# shudian_datapath.net
KiCad netlist of a schematic drawn in Altium Designer
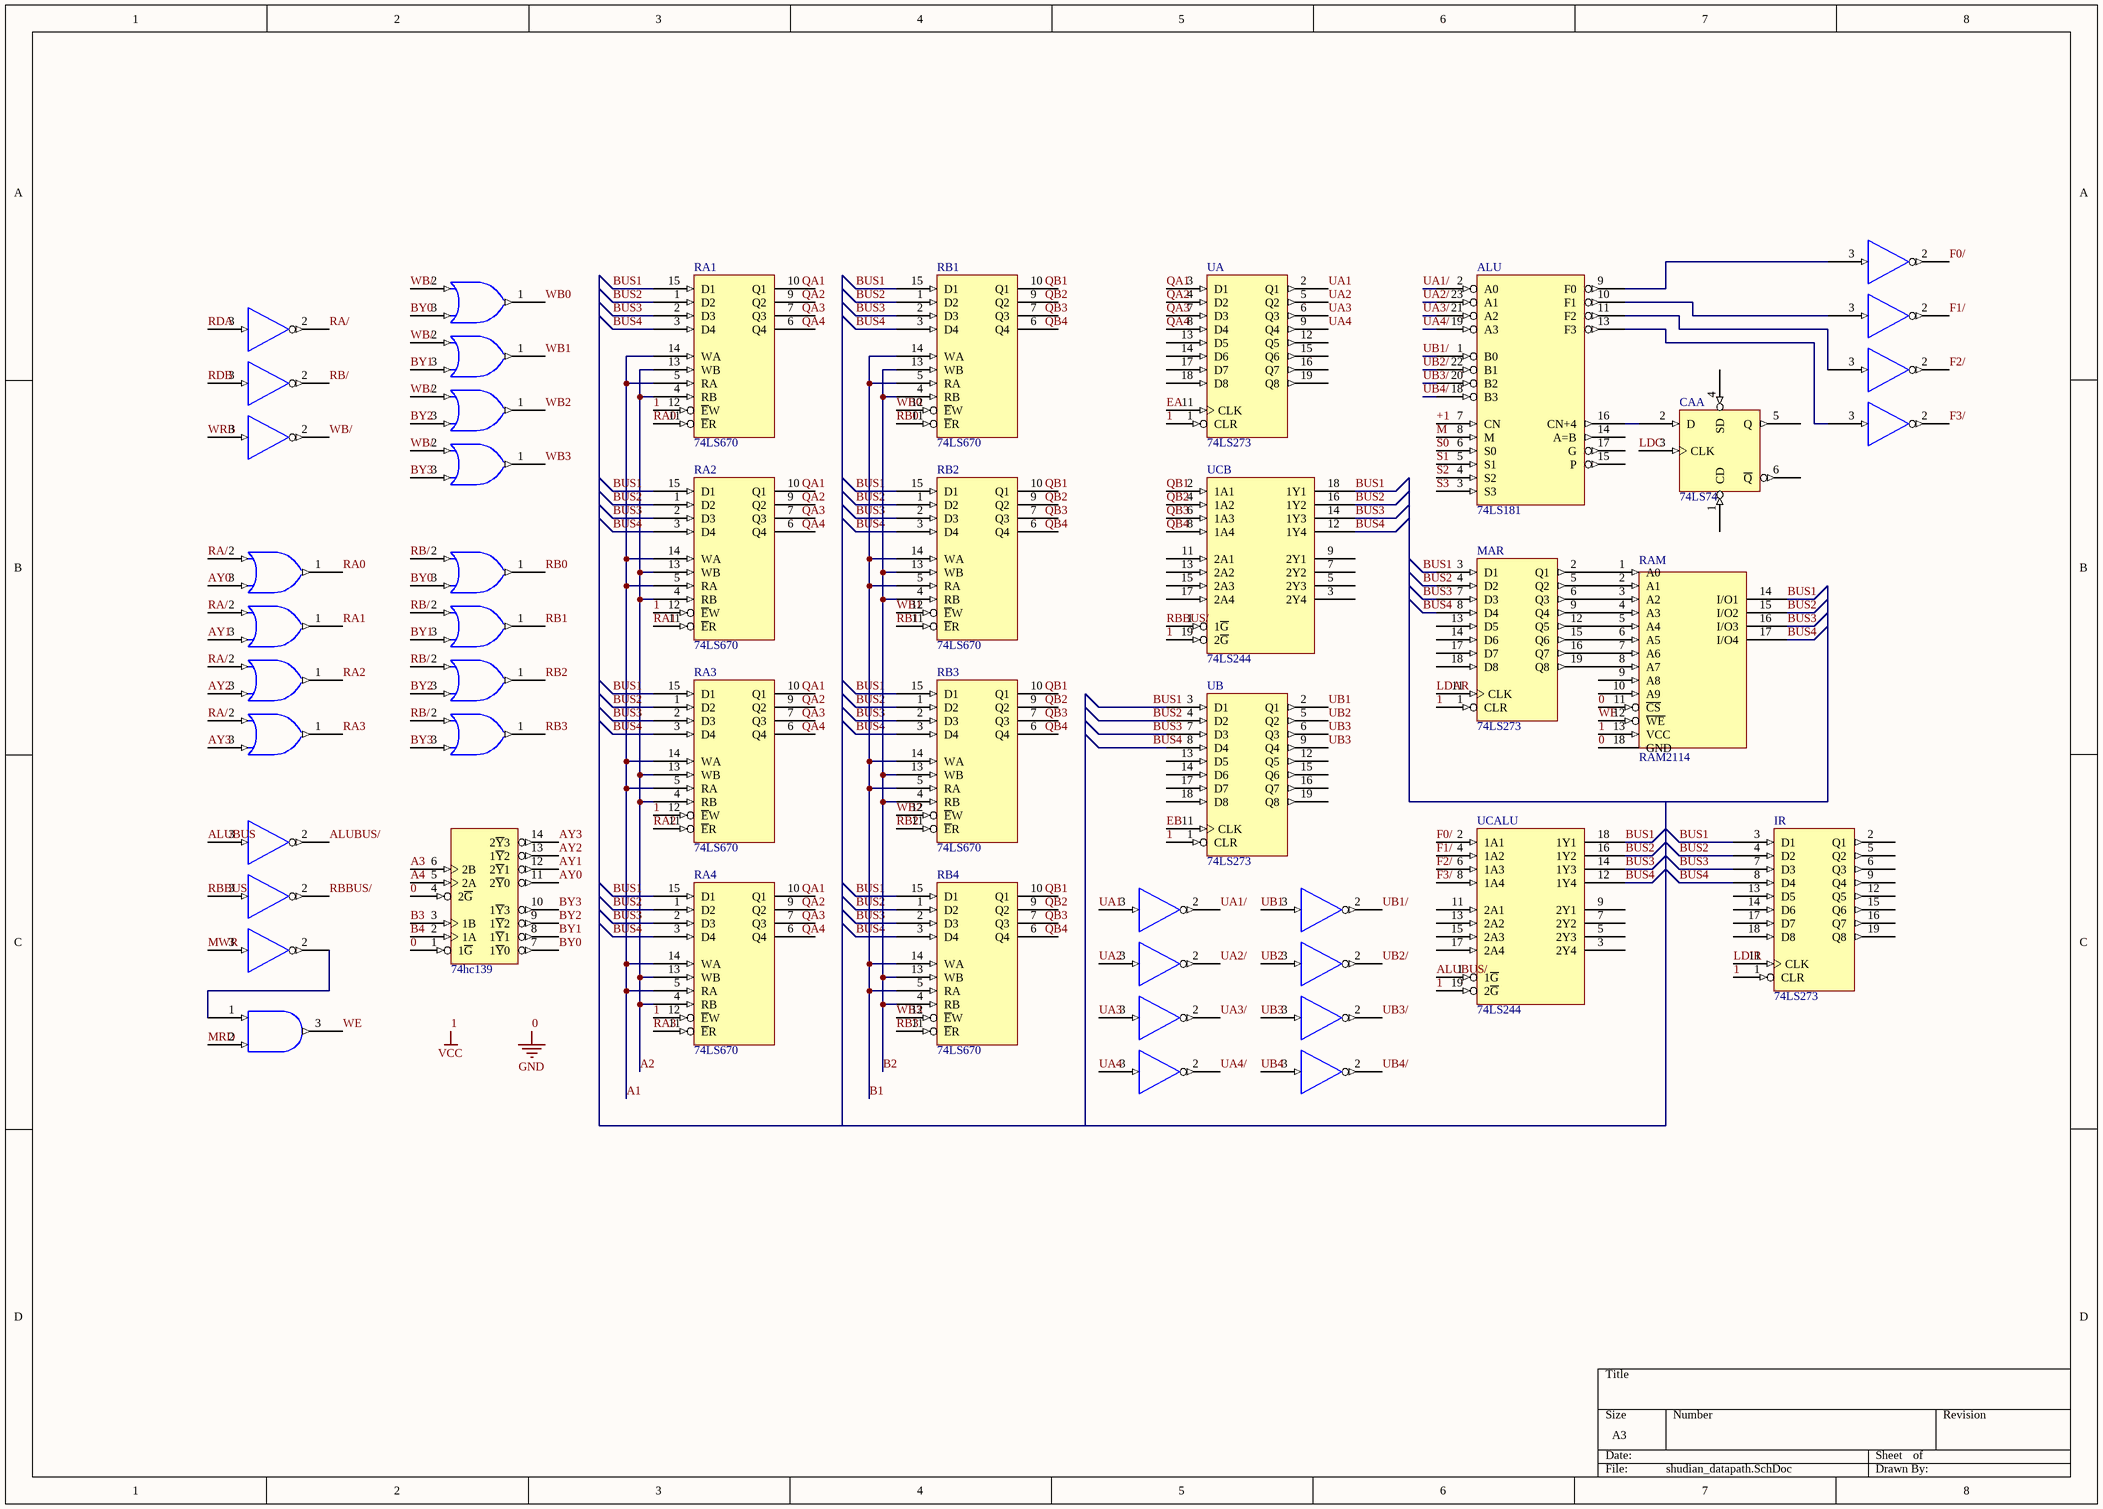
[diagram p0: shudian_datapath.SchDoc]

(export (version "E")
  (design (tool "Eeschema 10.0.6"))
  (components
    (comp (ref "*1") (value "not") (libsource (lib "数电") (part "not")))
    (comp (ref "*2") (value "not") (libsource (lib "数电") (part "not")))
    (comp (ref "*3") (value "not") (libsource (lib "数电") (part "not")))
    (comp (ref "*4-2") (value "74hc139") (libsource (lib "数电") (part "74hc139")))
    (comp (ref "*21") (value "and") (libsource (lib "数电") (part "and")))
    (comp (ref "*or5") (value "or") (libsource (lib "数电") (part "or")))
    (comp (ref "ALU") (value "74LS181") (footprint "DIP-24") (libsource (lib "数电") (part "74LS181")))
    (comp (ref "CA") (value "74LS74") (footprint "DIP-14") (libsource (lib "数电") (part "74LS74")))
    (comp (ref "IR") (value "74LS273") (footprint "DIP-20") (libsource (lib "数电") (part "74LS273")))
    (comp (ref "MAR") (value "74LS273") (footprint "DIP-20") (libsource (lib "数电") (part "74LS273")))
    (comp (ref "not1") (value "not") (libsource (lib "数电") (part "not")))
    (comp (ref "not2") (value "not") (libsource (lib "数电") (part "not")))
    (comp (ref "not3") (value "not") (libsource (lib "数电") (part "not")))
    (comp (ref "not4") (value "not") (libsource (lib "数电") (part "not")))
    (comp (ref "not5") (value "not") (libsource (lib "数电") (part "not")))
    (comp (ref "not6") (value "not") (libsource (lib "数电") (part "not")))
    (comp (ref "not7") (value "not") (libsource (lib "数电") (part "not")))
    (comp (ref "not8") (value "not") (libsource (lib "数电") (part "not")))
    (comp (ref "not9") (value "not") (libsource (lib "数电") (part "not")))
    (comp (ref "not10") (value "not") (libsource (lib "数电") (part "not")))
    (comp (ref "not11") (value "not") (libsource (lib "数电") (part "not")))
    (comp (ref "not12") (value "not") (libsource (lib "数电") (part "not")))
    (comp (ref "not13") (value "not") (libsource (lib "数电") (part "not")))
    (comp (ref "not14") (value "not") (libsource (lib "数电") (part "not")))
    (comp (ref "not15") (value "not") (libsource (lib "数电") (part "not")))
    (comp (ref "or1") (value "or") (libsource (lib "数电") (part "or")))
    (comp (ref "or2") (value "or") (libsource (lib "数电") (part "or")))
    (comp (ref "or3") (value "or") (libsource (lib "数电") (part "or")))
    (comp (ref "or4") (value "or") (libsource (lib "数电") (part "or")))
    (comp (ref "or6") (value "or") (libsource (lib "数电") (part "or")))
    (comp (ref "or7") (value "or") (libsource (lib "数电") (part "or")))
    (comp (ref "or8") (value "or") (libsource (lib "数电") (part "or")))
    (comp (ref "or9") (value "or") (libsource (lib "数电") (part "or")))
    (comp (ref "or10") (value "or") (libsource (lib "数电") (part "or")))
    (comp (ref "or11") (value "or") (libsource (lib "数电") (part "or")))
    (comp (ref "or12") (value "or") (libsource (lib "数电") (part "or")))
    (comp (ref "RA1")
      (value "74LS670")
      (footprint "DIP-16")
      (libsource (lib "digital system design") (part "74LS670"))
    )
    (comp (ref "RA2")
      (value "74LS670")
      (footprint "DIP-16")
      (libsource (lib "digital system design") (part "74LS670"))
    )
    (comp (ref "RA3")
      (value "74LS670")
      (footprint "DIP-16")
      (libsource (lib "digital system design") (part "74LS670"))
    )
    (comp (ref "RA4")
      (value "74LS670")
      (footprint "DIP-16")
      (libsource (lib "digital system design") (part "74LS670"))
    )
    (comp (ref "RAM") (value "RAM2114") (libsource (lib "数电") (part "RAM2114")))
    (comp (ref "RB1")
      (value "74LS670")
      (footprint "DIP-16")
      (libsource (lib "digital system design") (part "74LS670"))
    )
    (comp (ref "RB2")
      (value "74LS670")
      (footprint "DIP-16")
      (libsource (lib "digital system design") (part "74LS670"))
    )
    (comp (ref "RB3")
      (value "74LS670")
      (footprint "DIP-16")
      (libsource (lib "digital system design") (part "74LS670"))
    )
    (comp (ref "RB4")
      (value "74LS670")
      (footprint "DIP-16")
      (libsource (lib "digital system design") (part "74LS670"))
    )
    (comp (ref "UA") (value "74LS273") (footprint "DIP-20") (libsource (lib "数电") (part "74LS273")))
    (comp (ref "UB") (value "74LS273") (footprint "DIP-20") (libsource (lib "数电") (part "74LS273")))
    (comp (ref "UCALU") (value "74LS244") (footprint "DIP-20") (libsource (lib "数电") (part "74LS244")))
    (comp (ref "UCB") (value "74LS244") (footprint "DIP-20") (libsource (lib "数电") (part "74LS244")))
  )
  (nets
    (net (code "1") (name "/+1") (class "Default")
      (node (ref "ALU") (pin "7") (pinfunction "CN_7") (pintype "input"))
    )
    (net (code "2") (name "/A1") (class "Default")
      (node (ref "RA1") (pin "14") (pinfunction "WA_14") (pintype "input"))
      (node (ref "RA1") (pin "5") (pinfunction "RA_5") (pintype "input"))
      (node (ref "RA2") (pin "14") (pinfunction "WA_14") (pintype "input"))
      (node (ref "RA2") (pin "5") (pinfunction "RA_5") (pintype "input"))
      (node (ref "RA3") (pin "14") (pinfunction "WA_14") (pintype "input"))
      (node (ref "RA3") (pin "5") (pinfunction "RA_5") (pintype "input"))
      (node (ref "RA4") (pin "14") (pinfunction "WA_14") (pintype "input"))
      (node (ref "RA4") (pin "5") (pinfunction "RA_5") (pintype "input"))
    )
    (net (code "3") (name "/A2") (class "Default")
      (node (ref "RA1") (pin "13") (pinfunction "WB_13") (pintype "input"))
      (node (ref "RA1") (pin "4") (pinfunction "RB_4") (pintype "input"))
      (node (ref "RA2") (pin "13") (pinfunction "WB_13") (pintype "input"))
      (node (ref "RA2") (pin "4") (pinfunction "RB_4") (pintype "input"))
      (node (ref "RA3") (pin "13") (pinfunction "WB_13") (pintype "input"))
      (node (ref "RA3") (pin "4") (pinfunction "RB_4") (pintype "input"))
      (node (ref "RA4") (pin "13") (pinfunction "WB_13") (pintype "input"))
      (node (ref "RA4") (pin "4") (pinfunction "RB_4") (pintype "input"))
    )
    (net (code "4") (name "/A3") (class "Default")
      (node (ref "*4-2") (pin "6") (pinfunction "2B_6") (pintype "input"))
    )
    (net (code "5") (name "/A4") (class "Default")
      (node (ref "*4-2") (pin "5") (pinfunction "2A_5") (pintype "input"))
    )
    (net (code "6") (name "/ALUBUS") (class "Default") (node (ref "*1") (pin "3") (pintype "input")))
    (net (code "7") (name "/ALUBUS{slash}") (class "Default")
      (node (ref "*1") (pin "2") (pintype "output"))
      (node (ref "UCALU") (pin "1") (pinfunction "1~{G}_1") (pintype "input"))
    )
    (net (code "8") (name "/AY0") (class "Default")
      (node (ref "*4-2") (pin "11") (pinfunction "2~{Y}0_11") (pintype "output"))
      (node (ref "or1") (pin "3") (pintype "input"))
    )
    (net (code "9") (name "/AY1") (class "Default")
      (node (ref "*4-2") (pin "12") (pinfunction "2~{Y}1_12") (pintype "output"))
      (node (ref "or2") (pin "3") (pintype "input"))
    )
    (net (code "10") (name "/AY2") (class "Default")
      (node (ref "*4-2") (pin "13") (pinfunction "1~{Y}2_13") (pintype "output"))
      (node (ref "or3") (pin "3") (pintype "input"))
    )
    (net (code "11") (name "/AY3") (class "Default")
      (node (ref "*4-2") (pin "14") (pinfunction "2~{Y}3_14") (pintype "output"))
      (node (ref "or4") (pin "3") (pintype "input"))
    )
    (net (code "12") (name "/B1") (class "Default")
      (node (ref "RB1") (pin "14") (pinfunction "WA_14") (pintype "input"))
      (node (ref "RB1") (pin "5") (pinfunction "RA_5") (pintype "input"))
      (node (ref "RB2") (pin "14") (pinfunction "WA_14") (pintype "input"))
      (node (ref "RB2") (pin "5") (pinfunction "RA_5") (pintype "input"))
      (node (ref "RB3") (pin "14") (pinfunction "WA_14") (pintype "input"))
      (node (ref "RB3") (pin "5") (pinfunction "RA_5") (pintype "input"))
      (node (ref "RB4") (pin "14") (pinfunction "WA_14") (pintype "input"))
      (node (ref "RB4") (pin "5") (pinfunction "RA_5") (pintype "input"))
    )
    (net (code "13") (name "/B2") (class "Default")
      (node (ref "RB1") (pin "13") (pinfunction "WB_13") (pintype "input"))
      (node (ref "RB1") (pin "4") (pinfunction "RB_4") (pintype "input"))
      (node (ref "RB2") (pin "13") (pinfunction "WB_13") (pintype "input"))
      (node (ref "RB2") (pin "4") (pinfunction "RB_4") (pintype "input"))
      (node (ref "RB3") (pin "13") (pinfunction "WB_13") (pintype "input"))
      (node (ref "RB3") (pin "4") (pinfunction "RB_4") (pintype "input"))
      (node (ref "RB4") (pin "13") (pinfunction "WB_13") (pintype "input"))
      (node (ref "RB4") (pin "4") (pinfunction "RB_4") (pintype "input"))
    )
    (net (code "14") (name "/B3") (class "Default")
      (node (ref "*4-2") (pin "3") (pinfunction "1B_3") (pintype "input"))
    )
    (net (code "15") (name "/B4") (class "Default")
      (node (ref "*4-2") (pin "2") (pinfunction "1A_2") (pintype "input"))
    )
    (net (code "16") (name "/BUS1") (class "Default")
      (node (ref "IR") (pin "3") (pinfunction "D1_3") (pintype "input"))
      (node (ref "MAR") (pin "3") (pinfunction "D1_3") (pintype "input"))
      (node (ref "RA1") (pin "15") (pinfunction "D1_15") (pintype "input"))
      (node (ref "RA2") (pin "15") (pinfunction "D1_15") (pintype "input"))
      (node (ref "RA3") (pin "15") (pinfunction "D1_15") (pintype "input"))
      (node (ref "RA4") (pin "15") (pinfunction "D1_15") (pintype "input"))
      (node (ref "RAM") (pin "14") (pinfunction "I/O1_14") (pintype "tri_state"))
      (node (ref "RB1") (pin "15") (pinfunction "D1_15") (pintype "input"))
      (node (ref "RB2") (pin "15") (pinfunction "D1_15") (pintype "input"))
      (node (ref "RB3") (pin "15") (pinfunction "D1_15") (pintype "input"))
      (node (ref "RB4") (pin "15") (pinfunction "D1_15") (pintype "input"))
      (node (ref "UB") (pin "3") (pinfunction "D1_3") (pintype "input"))
      (node (ref "UCALU") (pin "18") (pinfunction "1Y1_18") (pintype "tri_state"))
      (node (ref "UCB") (pin "18") (pinfunction "1Y1_18") (pintype "tri_state"))
    )
    (net (code "17") (name "/BUS2") (class "Default")
      (node (ref "IR") (pin "4") (pinfunction "D2_4") (pintype "input"))
      (node (ref "MAR") (pin "4") (pinfunction "D2_4") (pintype "input"))
      (node (ref "RA1") (pin "1") (pinfunction "D2_1") (pintype "input"))
      (node (ref "RA2") (pin "1") (pinfunction "D2_1") (pintype "input"))
      (node (ref "RA3") (pin "1") (pinfunction "D2_1") (pintype "input"))
      (node (ref "RA4") (pin "1") (pinfunction "D2_1") (pintype "input"))
      (node (ref "RAM") (pin "15") (pinfunction "I/O2_15") (pintype "tri_state"))
      (node (ref "RB1") (pin "1") (pinfunction "D2_1") (pintype "input"))
      (node (ref "RB2") (pin "1") (pinfunction "D2_1") (pintype "input"))
      (node (ref "RB3") (pin "1") (pinfunction "D2_1") (pintype "input"))
      (node (ref "RB4") (pin "1") (pinfunction "D2_1") (pintype "input"))
      (node (ref "UB") (pin "4") (pinfunction "D2_4") (pintype "input"))
      (node (ref "UCALU") (pin "16") (pinfunction "1Y2_16") (pintype "tri_state"))
      (node (ref "UCB") (pin "16") (pinfunction "1Y2_16") (pintype "tri_state"))
    )
    (net (code "18") (name "/BUS3") (class "Default")
      (node (ref "IR") (pin "7") (pinfunction "D3_7") (pintype "input"))
      (node (ref "MAR") (pin "7") (pinfunction "D3_7") (pintype "input"))
      (node (ref "RA1") (pin "2") (pinfunction "D3_2") (pintype "input"))
      (node (ref "RA2") (pin "2") (pinfunction "D3_2") (pintype "input"))
      (node (ref "RA3") (pin "2") (pinfunction "D3_2") (pintype "input"))
      (node (ref "RA4") (pin "2") (pinfunction "D3_2") (pintype "input"))
      (node (ref "RAM") (pin "16") (pinfunction "I/O3_16") (pintype "tri_state"))
      (node (ref "RB1") (pin "2") (pinfunction "D3_2") (pintype "input"))
      (node (ref "RB2") (pin "2") (pinfunction "D3_2") (pintype "input"))
      (node (ref "RB3") (pin "2") (pinfunction "D3_2") (pintype "input"))
      (node (ref "RB4") (pin "2") (pinfunction "D3_2") (pintype "input"))
      (node (ref "UB") (pin "7") (pinfunction "D3_7") (pintype "input"))
      (node (ref "UCALU") (pin "14") (pinfunction "1Y3_14") (pintype "tri_state"))
      (node (ref "UCB") (pin "14") (pinfunction "1Y3_14") (pintype "tri_state"))
    )
    (net (code "19") (name "/BUS4") (class "Default")
      (node (ref "IR") (pin "8") (pinfunction "D4_8") (pintype "input"))
      (node (ref "MAR") (pin "8") (pinfunction "D4_8") (pintype "input"))
      (node (ref "RA1") (pin "3") (pinfunction "D4_3") (pintype "input"))
      (node (ref "RA2") (pin "3") (pinfunction "D4_3") (pintype "input"))
      (node (ref "RA3") (pin "3") (pinfunction "D4_3") (pintype "input"))
      (node (ref "RA4") (pin "3") (pinfunction "D4_3") (pintype "input"))
      (node (ref "RAM") (pin "17") (pinfunction "I/O4_17") (pintype "tri_state"))
      (node (ref "RB1") (pin "3") (pinfunction "D4_3") (pintype "input"))
      (node (ref "RB2") (pin "3") (pinfunction "D4_3") (pintype "input"))
      (node (ref "RB3") (pin "3") (pinfunction "D4_3") (pintype "input"))
      (node (ref "RB4") (pin "3") (pinfunction "D4_3") (pintype "input"))
      (node (ref "UB") (pin "8") (pinfunction "D4_8") (pintype "input"))
      (node (ref "UCALU") (pin "12") (pinfunction "1Y4_12") (pintype "tri_state"))
      (node (ref "UCB") (pin "12") (pinfunction "1Y4_12") (pintype "tri_state"))
    )
    (net (code "20") (name "/BY0") (class "Default")
      (node (ref "*4-2") (pin "7") (pinfunction "1~{Y}0_7") (pintype "output"))
      (node (ref "*or5") (pin "3") (pintype "input"))
      (node (ref "or9") (pin "3") (pintype "input"))
    )
    (net (code "21") (name "/BY1") (class "Default")
      (node (ref "*4-2") (pin "8") (pinfunction "1~{Y}1_8") (pintype "output"))
      (node (ref "or10") (pin "3") (pintype "input"))
      (node (ref "or6") (pin "3") (pintype "input"))
    )
    (net (code "22") (name "/BY2") (class "Default")
      (node (ref "*4-2") (pin "9") (pinfunction "1~{Y}2_9") (pintype "output"))
      (node (ref "or11") (pin "3") (pintype "input"))
      (node (ref "or7") (pin "3") (pintype "input"))
    )
    (net (code "23") (name "/BY3") (class "Default")
      (node (ref "*4-2") (pin "10") (pinfunction "1~{Y}3_10") (pintype "output"))
      (node (ref "or12") (pin "3") (pintype "input"))
      (node (ref "or8") (pin "3") (pintype "input"))
    )
    (net (code "24") (name "/EA") (class "Default")
      (node (ref "UA") (pin "11") (pinfunction "CLK_11") (pintype "input"))
    )
    (net (code "25") (name "/EB") (class "Default")
      (node (ref "UB") (pin "11") (pinfunction "CLK_11") (pintype "input"))
    )
    (net (code "26") (name "/F0{slash}") (class "Default")
      (node (ref "UCALU") (pin "2") (pinfunction "1A1_2") (pintype "input"))
      (node (ref "not4") (pin "2") (pintype "output"))
    )
    (net (code "27") (name "/F1{slash}") (class "Default")
      (node (ref "UCALU") (pin "4") (pinfunction "1A2_4") (pintype "input"))
      (node (ref "not5") (pin "2") (pintype "output"))
    )
    (net (code "28") (name "/F2{slash}") (class "Default")
      (node (ref "UCALU") (pin "6") (pinfunction "1A3_6") (pintype "input"))
      (node (ref "not6") (pin "2") (pintype "output"))
    )
    (net (code "29") (name "/F3{slash}") (class "Default")
      (node (ref "UCALU") (pin "8") (pinfunction "1A4_8") (pintype "input"))
      (node (ref "not7") (pin "2") (pintype "output"))
    )
    (net (code "30") (name "/LDAR") (class "Default")
      (node (ref "MAR") (pin "11") (pinfunction "CLK_11") (pintype "input"))
    )
    (net (code "31") (name "/LDC") (class "Default")
      (node (ref "CA") (pin "3") (pinfunction "CLK_3") (pintype "input"))
    )
    (net (code "32") (name "/LDIR") (class "Default")
      (node (ref "IR") (pin "11") (pinfunction "CLK_11") (pintype "input"))
    )
    (net (code "33") (name "/M") (class "Default")
      (node (ref "ALU") (pin "8") (pinfunction "M_8") (pintype "input"))
    )
    (net (code "34") (name "/MRD") (class "Default") (node (ref "*21") (pin "2") (pintype "input")))
    (net (code "35") (name "/MWR") (class "Default") (node (ref "*3") (pin "3") (pintype "input")))
    (net (code "36") (name "/QA1") (class "Default")
      (node (ref "UA") (pin "3") (pinfunction "D1_3") (pintype "input"))
    )
    (net (code "37") (name "/QA2") (class "Default")
      (node (ref "UA") (pin "4") (pinfunction "D2_4") (pintype "input"))
    )
    (net (code "38") (name "/QA3") (class "Default")
      (node (ref "UA") (pin "7") (pinfunction "D3_7") (pintype "input"))
    )
    (net (code "39") (name "/QA4") (class "Default")
      (node (ref "UA") (pin "8") (pinfunction "D4_8") (pintype "input"))
    )
    (net (code "40") (name "/QB1") (class "Default")
      (node (ref "UCB") (pin "2") (pinfunction "1A1_2") (pintype "input"))
    )
    (net (code "41") (name "/QB2") (class "Default")
      (node (ref "UCB") (pin "4") (pinfunction "1A2_4") (pintype "input"))
    )
    (net (code "42") (name "/QB3") (class "Default")
      (node (ref "UCB") (pin "6") (pinfunction "1A3_6") (pintype "input"))
    )
    (net (code "43") (name "/QB4") (class "Default")
      (node (ref "UCB") (pin "8") (pinfunction "1A4_8") (pintype "input"))
    )
    (net (code "44") (name "/RA0") (class "Default")
      (node (ref "RA1") (pin "11") (pinfunction "~{E}R_11") (pintype "input"))
      (node (ref "or1") (pin "1") (pintype "output"))
    )
    (net (code "45") (name "/RA1") (class "Default")
      (node (ref "RA2") (pin "11") (pinfunction "~{E}R_11") (pintype "input"))
      (node (ref "or2") (pin "1") (pintype "output"))
    )
    (net (code "46") (name "/RA2") (class "Default")
      (node (ref "RA3") (pin "11") (pinfunction "~{E}R_11") (pintype "input"))
      (node (ref "or3") (pin "1") (pintype "output"))
    )
    (net (code "47") (name "/RA3") (class "Default")
      (node (ref "RA4") (pin "11") (pinfunction "~{E}R_11") (pintype "input"))
      (node (ref "or4") (pin "1") (pintype "output"))
    )
    (net (code "48") (name "/RA{slash}") (class "Default")
      (node (ref "not1") (pin "2") (pintype "output"))
      (node (ref "or1") (pin "2") (pintype "input"))
      (node (ref "or2") (pin "2") (pintype "input"))
      (node (ref "or3") (pin "2") (pintype "input"))
      (node (ref "or4") (pin "2") (pintype "input"))
    )
    (net (code "49") (name "/RB0") (class "Default")
      (node (ref "*or5") (pin "1") (pintype "output"))
      (node (ref "RB1") (pin "11") (pinfunction "~{E}R_11") (pintype "input"))
    )
    (net (code "50") (name "/RB1") (class "Default")
      (node (ref "RB2") (pin "11") (pinfunction "~{E}R_11") (pintype "input"))
      (node (ref "or6") (pin "1") (pintype "output"))
    )
    (net (code "51") (name "/RB2") (class "Default")
      (node (ref "RB3") (pin "11") (pinfunction "~{E}R_11") (pintype "input"))
      (node (ref "or7") (pin "1") (pintype "output"))
    )
    (net (code "52") (name "/RB3") (class "Default")
      (node (ref "RB4") (pin "11") (pinfunction "~{E}R_11") (pintype "input"))
      (node (ref "or8") (pin "1") (pintype "output"))
    )
    (net (code "53") (name "/RBBUS") (class "Default") (node (ref "*2") (pin "3") (pintype "input")))
    (net (code "54") (name "/RBBUS{slash}") (class "Default")
      (node (ref "*2") (pin "2") (pintype "output"))
      (node (ref "UCB") (pin "1") (pinfunction "1~{G}_1") (pintype "input"))
    )
    (net (code "55") (name "/RB{slash}") (class "Default")
      (node (ref "*or5") (pin "2") (pintype "input"))
      (node (ref "not2") (pin "2") (pintype "output"))
      (node (ref "or6") (pin "2") (pintype "input"))
      (node (ref "or7") (pin "2") (pintype "input"))
      (node (ref "or8") (pin "2") (pintype "input"))
    )
    (net (code "56") (name "/RDA") (class "Default") (node (ref "not1") (pin "3") (pintype "input")))
    (net (code "57") (name "/RDB") (class "Default") (node (ref "not2") (pin "3") (pintype "input")))
    (net (code "58") (name "/S0") (class "Default")
      (node (ref "ALU") (pin "6") (pinfunction "S0_6") (pintype "input"))
    )
    (net (code "59") (name "/S1") (class "Default")
      (node (ref "ALU") (pin "5") (pinfunction "S1_5") (pintype "input"))
    )
    (net (code "60") (name "/S2") (class "Default")
      (node (ref "ALU") (pin "4") (pinfunction "S2_4") (pintype "input"))
    )
    (net (code "61") (name "/S3") (class "Default")
      (node (ref "ALU") (pin "3") (pinfunction "S3_3") (pintype "input"))
    )
    (net (code "62") (name "/UA1") (class "Default")
      (node (ref "UA") (pin "2") (pinfunction "Q1_2") (pintype "output"))
      (node (ref "not8") (pin "3") (pintype "input"))
    )
    (net (code "63") (name "/UA1{slash}") (class "Default")
      (node (ref "ALU") (pin "2") (pinfunction "A0_2") (pintype "input"))
      (node (ref "not8") (pin "2") (pintype "output"))
    )
    (net (code "64") (name "/UA2") (class "Default")
      (node (ref "UA") (pin "5") (pinfunction "Q2_5") (pintype "output"))
      (node (ref "not9") (pin "3") (pintype "input"))
    )
    (net (code "65") (name "/UA2{slash}") (class "Default")
      (node (ref "ALU") (pin "23") (pinfunction "A1_23") (pintype "input"))
      (node (ref "not9") (pin "2") (pintype "output"))
    )
    (net (code "66") (name "/UA3") (class "Default")
      (node (ref "UA") (pin "6") (pinfunction "Q3_6") (pintype "output"))
      (node (ref "not10") (pin "3") (pintype "input"))
    )
    (net (code "67") (name "/UA3{slash}") (class "Default")
      (node (ref "ALU") (pin "21") (pinfunction "A2_21") (pintype "input"))
      (node (ref "not10") (pin "2") (pintype "output"))
    )
    (net (code "68") (name "/UA4") (class "Default")
      (node (ref "UA") (pin "9") (pinfunction "Q4_9") (pintype "output"))
      (node (ref "not11") (pin "3") (pintype "input"))
    )
    (net (code "69") (name "/UA4{slash}") (class "Default")
      (node (ref "ALU") (pin "19") (pinfunction "A3_19") (pintype "input"))
      (node (ref "not11") (pin "2") (pintype "output"))
    )
    (net (code "70") (name "/UB1") (class "Default")
      (node (ref "UB") (pin "2") (pinfunction "Q1_2") (pintype "output"))
      (node (ref "not12") (pin "3") (pintype "input"))
    )
    (net (code "71") (name "/UB1{slash}") (class "Default")
      (node (ref "ALU") (pin "1") (pinfunction "B0_1") (pintype "input"))
      (node (ref "not12") (pin "2") (pintype "output"))
    )
    (net (code "72") (name "/UB2") (class "Default")
      (node (ref "UB") (pin "5") (pinfunction "Q2_5") (pintype "output"))
      (node (ref "not13") (pin "3") (pintype "input"))
    )
    (net (code "73") (name "/UB2{slash}") (class "Default")
      (node (ref "ALU") (pin "22") (pinfunction "B1_22") (pintype "input"))
      (node (ref "not13") (pin "2") (pintype "output"))
    )
    (net (code "74") (name "/UB3") (class "Default")
      (node (ref "UB") (pin "6") (pinfunction "Q3_6") (pintype "output"))
      (node (ref "UB") (pin "9") (pinfunction "Q4_9") (pintype "output"))
      (node (ref "not14") (pin "3") (pintype "input"))
    )
    (net (code "75") (name "/UB3{slash}") (class "Default")
      (node (ref "ALU") (pin "20") (pinfunction "B2_20") (pintype "input"))
      (node (ref "not14") (pin "2") (pintype "output"))
    )
    (net (code "76") (name "/UB4") (class "Default") (node (ref "not15") (pin "3") (pintype "input")))
    (net (code "77") (name "/UB4{slash}") (class "Default")
      (node (ref "ALU") (pin "18") (pinfunction "B3_18") (pintype "input"))
      (node (ref "not15") (pin "2") (pintype "output"))
    )
    (net (code "78") (name "/WB0") (class "Default")
      (node (ref "RB1") (pin "12") (pinfunction "~{E}W_12") (pintype "input"))
      (node (ref "or9") (pin "1") (pintype "output"))
    )
    (net (code "79") (name "/WB1") (class "Default")
      (node (ref "RB2") (pin "12") (pinfunction "~{E}W_12") (pintype "input"))
      (node (ref "or10") (pin "1") (pintype "output"))
    )
    (net (code "80") (name "/WB2") (class "Default")
      (node (ref "RB3") (pin "12") (pinfunction "~{E}W_12") (pintype "input"))
      (node (ref "or11") (pin "1") (pintype "output"))
    )
    (net (code "81") (name "/WB3") (class "Default")
      (node (ref "RB4") (pin "12") (pinfunction "~{E}W_12") (pintype "input"))
      (node (ref "or12") (pin "1") (pintype "output"))
    )
    (net (code "82") (name "/WB{slash}") (class "Default")
      (node (ref "not3") (pin "2") (pintype "output"))
      (node (ref "or10") (pin "2") (pintype "input"))
      (node (ref "or11") (pin "2") (pintype "input"))
      (node (ref "or12") (pin "2") (pintype "input"))
      (node (ref "or9") (pin "2") (pintype "input"))
    )
    (net (code "83") (name "/WE") (class "Default")
      (node (ref "*21") (pin "3") (pintype "output"))
      (node (ref "RAM") (pin "12") (pinfunction "~{WE}_12") (pintype "input"))
    )
    (net (code "84") (name "/WRB") (class "Default") (node (ref "not3") (pin "3") (pintype "input")))
    (net (code "85") (name "GND") (class "Default")
      (node (ref "*4-2") (pin "1") (pinfunction "1~{G}_1") (pintype "input"))
      (node (ref "*4-2") (pin "4") (pinfunction "2~{G}_4") (pintype "input"))
      (node (ref "ALU") (pin "12") (pinfunction "GND_12") (pintype "power_in"))
      (node (ref "CA") (pin "7") (pinfunction "GND_7") (pintype "power_in"))
      (node (ref "IR") (pin "10") (pinfunction "GND_10") (pintype "power_in"))
      (node (ref "MAR") (pin "10") (pinfunction "GND_10") (pintype "power_in"))
      (node (ref "RA1") (pin "8") (pinfunction "GND_8") (pintype "power_in"))
      (node (ref "RA2") (pin "8") (pinfunction "GND_8") (pintype "power_in"))
      (node (ref "RA3") (pin "8") (pinfunction "GND_8") (pintype "power_in"))
      (node (ref "RA4") (pin "8") (pinfunction "GND_8") (pintype "power_in"))
      (node (ref "RAM") (pin "11") (pinfunction "~{CS}_11") (pintype "input"))
      (node (ref "RAM") (pin "18") (pinfunction "GND_18") (pintype "power_in"))
      (node (ref "RB1") (pin "8") (pinfunction "GND_8") (pintype "power_in"))
      (node (ref "RB2") (pin "8") (pinfunction "GND_8") (pintype "power_in"))
      (node (ref "RB3") (pin "8") (pinfunction "GND_8") (pintype "power_in"))
      (node (ref "RB4") (pin "8") (pinfunction "GND_8") (pintype "power_in"))
      (node (ref "UA") (pin "10") (pinfunction "GND_10") (pintype "power_in"))
      (node (ref "UB") (pin "10") (pinfunction "GND_10") (pintype "power_in"))
      (node (ref "UCALU") (pin "10") (pinfunction "GND_10") (pintype "power_in"))
      (node (ref "UCB") (pin "10") (pinfunction "GND_10") (pintype "power_in"))
    )
    (net (code "86") (name "Net-(*21-Pad1)") (class "Default")
      (node (ref "*21") (pin "1") (pintype "input"))
      (node (ref "*3") (pin "2") (pintype "output"))
    )
    (net (code "87") (name "Net-(ALU-CN+4)") (class "Default")
      (node (ref "ALU") (pin "16") (pinfunction "CN+4_16") (pintype "output"))
      (node (ref "CA") (pin "2") (pinfunction "D_2") (pintype "input"))
    )
    (net (code "88") (name "Net-(ALU-F0)") (class "Default")
      (node (ref "ALU") (pin "9") (pinfunction "F0_9") (pintype "output"))
      (node (ref "not4") (pin "3") (pintype "input"))
    )
    (net (code "89") (name "Net-(ALU-F1)") (class "Default")
      (node (ref "ALU") (pin "10") (pinfunction "F1_10") (pintype "output"))
      (node (ref "not5") (pin "3") (pintype "input"))
    )
    (net (code "90") (name "Net-(ALU-F2)") (class "Default")
      (node (ref "ALU") (pin "11") (pinfunction "F2_11") (pintype "output"))
      (node (ref "not6") (pin "3") (pintype "input"))
    )
    (net (code "91") (name "Net-(ALU-F3)") (class "Default")
      (node (ref "ALU") (pin "13") (pinfunction "F3_13") (pintype "output"))
      (node (ref "not7") (pin "3") (pintype "input"))
    )
    (net (code "92") (name "Net-(MAR-Q1)") (class "Default")
      (node (ref "MAR") (pin "2") (pinfunction "Q1_2") (pintype "output"))
      (node (ref "RAM") (pin "1") (pinfunction "A0_1") (pintype "input"))
    )
    (net (code "93") (name "Net-(MAR-Q2)") (class "Default")
      (node (ref "MAR") (pin "5") (pinfunction "Q2_5") (pintype "output"))
      (node (ref "RAM") (pin "2") (pinfunction "A1_2") (pintype "input"))
    )
    (net (code "94") (name "Net-(MAR-Q3)") (class "Default")
      (node (ref "MAR") (pin "6") (pinfunction "Q3_6") (pintype "output"))
      (node (ref "RAM") (pin "3") (pinfunction "A2_3") (pintype "input"))
    )
    (net (code "95") (name "Net-(MAR-Q4)") (class "Default")
      (node (ref "MAR") (pin "9") (pinfunction "Q4_9") (pintype "output"))
      (node (ref "RAM") (pin "4") (pinfunction "A3_4") (pintype "input"))
    )
    (net (code "96") (name "Net-(MAR-Q5)") (class "Default")
      (node (ref "MAR") (pin "12") (pinfunction "Q5_12") (pintype "output"))
      (node (ref "RAM") (pin "5") (pinfunction "A4_5") (pintype "input"))
    )
    (net (code "97") (name "Net-(MAR-Q6)") (class "Default")
      (node (ref "MAR") (pin "15") (pinfunction "Q6_15") (pintype "output"))
      (node (ref "RAM") (pin "6") (pinfunction "A5_6") (pintype "input"))
    )
    (net (code "98") (name "Net-(MAR-Q7)") (class "Default")
      (node (ref "MAR") (pin "16") (pinfunction "Q7_16") (pintype "output"))
      (node (ref "RAM") (pin "7") (pinfunction "A6_7") (pintype "input"))
    )
    (net (code "99") (name "Net-(MAR-Q8)") (class "Default")
      (node (ref "MAR") (pin "19") (pinfunction "Q8_19") (pintype "output"))
      (node (ref "RAM") (pin "8") (pinfunction "A7_8") (pintype "input"))
    )
    (net (code "100") (name "VCC") (class "Default")
      (node (ref "ALU") (pin "24") (pinfunction "VCC_24") (pintype "power_in"))
      (node (ref "CA") (pin "14") (pinfunction "VCC_14") (pintype "power_in"))
      (node (ref "IR") (pin "1") (pinfunction "CLR_1") (pintype "input"))
      (node (ref "IR") (pin "20") (pinfunction "VCC_20") (pintype "power_in"))
      (node (ref "MAR") (pin "1") (pinfunction "CLR_1") (pintype "input"))
      (node (ref "MAR") (pin "20") (pinfunction "VCC_20") (pintype "power_in"))
      (node (ref "RA1") (pin "12") (pinfunction "~{E}W_12") (pintype "input"))
      (node (ref "RA1") (pin "16") (pinfunction "VCC_16") (pintype "power_in"))
      (node (ref "RA2") (pin "12") (pinfunction "~{E}W_12") (pintype "input"))
      (node (ref "RA2") (pin "16") (pinfunction "VCC_16") (pintype "power_in"))
      (node (ref "RA3") (pin "12") (pinfunction "~{E}W_12") (pintype "input"))
      (node (ref "RA3") (pin "16") (pinfunction "VCC_16") (pintype "power_in"))
      (node (ref "RA4") (pin "12") (pinfunction "~{E}W_12") (pintype "input"))
      (node (ref "RA4") (pin "16") (pinfunction "VCC_16") (pintype "power_in"))
      (node (ref "RAM") (pin "13") (pinfunction "VCC_13") (pintype "input"))
      (node (ref "RB1") (pin "16") (pinfunction "VCC_16") (pintype "power_in"))
      (node (ref "RB2") (pin "16") (pinfunction "VCC_16") (pintype "power_in"))
      (node (ref "RB3") (pin "16") (pinfunction "VCC_16") (pintype "power_in"))
      (node (ref "RB4") (pin "16") (pinfunction "VCC_16") (pintype "power_in"))
      (node (ref "UA") (pin "1") (pinfunction "CLR_1") (pintype "input"))
      (node (ref "UA") (pin "20") (pinfunction "VCC_20") (pintype "power_in"))
      (node (ref "UB") (pin "1") (pinfunction "CLR_1") (pintype "input"))
      (node (ref "UB") (pin "20") (pinfunction "VCC_20") (pintype "power_in"))
      (node (ref "UCALU") (pin "19") (pinfunction "2~{G}_19") (pintype "input"))
      (node (ref "UCALU") (pin "20") (pinfunction "VCC_20") (pintype "power_in"))
      (node (ref "UCB") (pin "19") (pinfunction "2~{G}_19") (pintype "input"))
      (node (ref "UCB") (pin "20") (pinfunction "VCC_20") (pintype "power_in"))
    )
    (net (code "101") (name "unconnected-(ALU-A=B-Pad14)") (class "Default")
      (node (ref "ALU") (pin "14") (pinfunction "A=B_14") (pintype "output"))
    )
    (net (code "102") (name "unconnected-(ALU-G-Pad17)") (class "Default")
      (node (ref "ALU") (pin "17") (pinfunction "G_17") (pintype "output"))
    )
    (net (code "103") (name "unconnected-(ALU-P-Pad15)") (class "Default")
      (node (ref "ALU") (pin "15") (pinfunction "P_15") (pintype "output"))
    )
    (net (code "104") (name "unconnected-(CAA-CD-Pad1)") (class "Default")
      (node (ref "CA") (pin "1") (pinfunction "CD_1") (pintype "input"))
    )
    (net (code "105") (name "unconnected-(CAA-Q-Pad5)") (class "Default")
      (node (ref "CA") (pin "5") (pinfunction "Q_5") (pintype "output"))
    )
    (net (code "106") (name "unconnected-(CAA-SD-Pad4)") (class "Default")
      (node (ref "CA") (pin "4") (pinfunction "SD_4") (pintype "input"))
    )
    (net (code "107") (name "unconnected-(CAA-~{Q}-Pad6)") (class "Default")
      (node (ref "CA") (pin "6") (pinfunction "~{Q}_6") (pintype "output"))
    )
    (net (code "108") (name "unconnected-(IR-D5-Pad13)") (class "Default")
      (node (ref "IR") (pin "13") (pinfunction "D5_13") (pintype "input"))
    )
    (net (code "109") (name "unconnected-(IR-D6-Pad14)") (class "Default")
      (node (ref "IR") (pin "14") (pinfunction "D6_14") (pintype "input"))
    )
    (net (code "110") (name "unconnected-(IR-D7-Pad17)") (class "Default")
      (node (ref "IR") (pin "17") (pinfunction "D7_17") (pintype "input"))
    )
    (net (code "111") (name "unconnected-(IR-D8-Pad18)") (class "Default")
      (node (ref "IR") (pin "18") (pinfunction "D8_18") (pintype "input"))
    )
    (net (code "112") (name "unconnected-(IR-Q1-Pad2)") (class "Default")
      (node (ref "IR") (pin "2") (pinfunction "Q1_2") (pintype "output"))
    )
    (net (code "113") (name "unconnected-(IR-Q2-Pad5)") (class "Default")
      (node (ref "IR") (pin "5") (pinfunction "Q2_5") (pintype "output"))
    )
    (net (code "114") (name "unconnected-(IR-Q3-Pad6)") (class "Default")
      (node (ref "IR") (pin "6") (pinfunction "Q3_6") (pintype "output"))
    )
    (net (code "115") (name "unconnected-(IR-Q4-Pad9)") (class "Default")
      (node (ref "IR") (pin "9") (pinfunction "Q4_9") (pintype "output"))
    )
    (net (code "116") (name "unconnected-(IR-Q5-Pad12)") (class "Default")
      (node (ref "IR") (pin "12") (pinfunction "Q5_12") (pintype "output"))
    )
    (net (code "117") (name "unconnected-(IR-Q6-Pad15)") (class "Default")
      (node (ref "IR") (pin "15") (pinfunction "Q6_15") (pintype "output"))
    )
    (net (code "118") (name "unconnected-(IR-Q7-Pad16)") (class "Default")
      (node (ref "IR") (pin "16") (pinfunction "Q7_16") (pintype "output"))
    )
    (net (code "119") (name "unconnected-(IR-Q8-Pad19)") (class "Default")
      (node (ref "IR") (pin "19") (pinfunction "Q8_19") (pintype "output"))
    )
    (net (code "120") (name "unconnected-(MAR-D5-Pad13)") (class "Default")
      (node (ref "MAR") (pin "13") (pinfunction "D5_13") (pintype "input"))
    )
    (net (code "121") (name "unconnected-(MAR-D6-Pad14)") (class "Default")
      (node (ref "MAR") (pin "14") (pinfunction "D6_14") (pintype "input"))
    )
    (net (code "122") (name "unconnected-(MAR-D7-Pad17)") (class "Default")
      (node (ref "MAR") (pin "17") (pinfunction "D7_17") (pintype "input"))
    )
    (net (code "123") (name "unconnected-(MAR-D8-Pad18)") (class "Default")
      (node (ref "MAR") (pin "18") (pinfunction "D8_18") (pintype "input"))
    )
    (net (code "124") (name "unconnected-(RA1-Q1-Pad10)") (class "Default")
      (node (ref "RA1") (pin "10") (pinfunction "Q1_10") (pintype "tri_state"))
    )
    (net (code "125") (name "unconnected-(RA1-Q2-Pad9)") (class "Default")
      (node (ref "RA1") (pin "9") (pinfunction "Q2_9") (pintype "tri_state"))
    )
    (net (code "126") (name "unconnected-(RA1-Q3-Pad7)") (class "Default")
      (node (ref "RA1") (pin "7") (pinfunction "Q3_7") (pintype "tri_state"))
    )
    (net (code "127") (name "unconnected-(RA1-Q4-Pad6)") (class "Default")
      (node (ref "RA1") (pin "6") (pinfunction "Q4_6") (pintype "tri_state"))
    )
    (net (code "128") (name "unconnected-(RA2-Q1-Pad10)") (class "Default")
      (node (ref "RA2") (pin "10") (pinfunction "Q1_10") (pintype "tri_state"))
    )
    (net (code "129") (name "unconnected-(RA2-Q2-Pad9)") (class "Default")
      (node (ref "RA2") (pin "9") (pinfunction "Q2_9") (pintype "tri_state"))
    )
    (net (code "130") (name "unconnected-(RA2-Q3-Pad7)") (class "Default")
      (node (ref "RA2") (pin "7") (pinfunction "Q3_7") (pintype "tri_state"))
    )
    (net (code "131") (name "unconnected-(RA2-Q4-Pad6)") (class "Default")
      (node (ref "RA2") (pin "6") (pinfunction "Q4_6") (pintype "tri_state"))
    )
    (net (code "132") (name "unconnected-(RA3-Q1-Pad10)") (class "Default")
      (node (ref "RA3") (pin "10") (pinfunction "Q1_10") (pintype "tri_state"))
    )
    (net (code "133") (name "unconnected-(RA3-Q2-Pad9)") (class "Default")
      (node (ref "RA3") (pin "9") (pinfunction "Q2_9") (pintype "tri_state"))
    )
    (net (code "134") (name "unconnected-(RA3-Q3-Pad7)") (class "Default")
      (node (ref "RA3") (pin "7") (pinfunction "Q3_7") (pintype "tri_state"))
    )
    (net (code "135") (name "unconnected-(RA3-Q4-Pad6)") (class "Default")
      (node (ref "RA3") (pin "6") (pinfunction "Q4_6") (pintype "tri_state"))
    )
    (net (code "136") (name "unconnected-(RA4-Q1-Pad10)") (class "Default")
      (node (ref "RA4") (pin "10") (pinfunction "Q1_10") (pintype "tri_state"))
    )
    (net (code "137") (name "unconnected-(RA4-Q2-Pad9)") (class "Default")
      (node (ref "RA4") (pin "9") (pinfunction "Q2_9") (pintype "tri_state"))
    )
    (net (code "138") (name "unconnected-(RA4-Q3-Pad7)") (class "Default")
      (node (ref "RA4") (pin "7") (pinfunction "Q3_7") (pintype "tri_state"))
    )
    (net (code "139") (name "unconnected-(RA4-Q4-Pad6)") (class "Default")
      (node (ref "RA4") (pin "6") (pinfunction "Q4_6") (pintype "tri_state"))
    )
    (net (code "140") (name "unconnected-(RAM-A8-Pad9)") (class "Default")
      (node (ref "RAM") (pin "9") (pinfunction "A8_9") (pintype "input"))
    )
    (net (code "141") (name "unconnected-(RAM-A9-Pad10)") (class "Default")
      (node (ref "RAM") (pin "10") (pinfunction "A9_10") (pintype "input"))
    )
    (net (code "142") (name "unconnected-(RB1-Q1-Pad10)") (class "Default")
      (node (ref "RB1") (pin "10") (pinfunction "Q1_10") (pintype "tri_state"))
    )
    (net (code "143") (name "unconnected-(RB1-Q2-Pad9)") (class "Default")
      (node (ref "RB1") (pin "9") (pinfunction "Q2_9") (pintype "tri_state"))
    )
    (net (code "144") (name "unconnected-(RB1-Q3-Pad7)") (class "Default")
      (node (ref "RB1") (pin "7") (pinfunction "Q3_7") (pintype "tri_state"))
    )
    (net (code "145") (name "unconnected-(RB1-Q4-Pad6)") (class "Default")
      (node (ref "RB1") (pin "6") (pinfunction "Q4_6") (pintype "tri_state"))
    )
    (net (code "146") (name "unconnected-(RB2-Q1-Pad10)") (class "Default")
      (node (ref "RB2") (pin "10") (pinfunction "Q1_10") (pintype "tri_state"))
    )
    (net (code "147") (name "unconnected-(RB2-Q2-Pad9)") (class "Default")
      (node (ref "RB2") (pin "9") (pinfunction "Q2_9") (pintype "tri_state"))
    )
    (net (code "148") (name "unconnected-(RB2-Q3-Pad7)") (class "Default")
      (node (ref "RB2") (pin "7") (pinfunction "Q3_7") (pintype "tri_state"))
    )
    (net (code "149") (name "unconnected-(RB2-Q4-Pad6)") (class "Default")
      (node (ref "RB2") (pin "6") (pinfunction "Q4_6") (pintype "tri_state"))
    )
    (net (code "150") (name "unconnected-(RB3-Q1-Pad10)") (class "Default")
      (node (ref "RB3") (pin "10") (pinfunction "Q1_10") (pintype "tri_state"))
    )
    (net (code "151") (name "unconnected-(RB3-Q2-Pad9)") (class "Default")
      (node (ref "RB3") (pin "9") (pinfunction "Q2_9") (pintype "tri_state"))
    )
    (net (code "152") (name "unconnected-(RB3-Q3-Pad7)") (class "Default")
      (node (ref "RB3") (pin "7") (pinfunction "Q3_7") (pintype "tri_state"))
    )
    (net (code "153") (name "unconnected-(RB3-Q4-Pad6)") (class "Default")
      (node (ref "RB3") (pin "6") (pinfunction "Q4_6") (pintype "tri_state"))
    )
    (net (code "154") (name "unconnected-(RB4-Q1-Pad10)") (class "Default")
      (node (ref "RB4") (pin "10") (pinfunction "Q1_10") (pintype "tri_state"))
    )
    (net (code "155") (name "unconnected-(RB4-Q2-Pad9)") (class "Default")
      (node (ref "RB4") (pin "9") (pinfunction "Q2_9") (pintype "tri_state"))
    )
    (net (code "156") (name "unconnected-(RB4-Q3-Pad7)") (class "Default")
      (node (ref "RB4") (pin "7") (pinfunction "Q3_7") (pintype "tri_state"))
    )
    (net (code "157") (name "unconnected-(RB4-Q4-Pad6)") (class "Default")
      (node (ref "RB4") (pin "6") (pinfunction "Q4_6") (pintype "tri_state"))
    )
    (net (code "158") (name "unconnected-(UA-D5-Pad13)") (class "Default")
      (node (ref "UA") (pin "13") (pinfunction "D5_13") (pintype "input"))
    )
    (net (code "159") (name "unconnected-(UA-D6-Pad14)") (class "Default")
      (node (ref "UA") (pin "14") (pinfunction "D6_14") (pintype "input"))
    )
    (net (code "160") (name "unconnected-(UA-D7-Pad17)") (class "Default")
      (node (ref "UA") (pin "17") (pinfunction "D7_17") (pintype "input"))
    )
    (net (code "161") (name "unconnected-(UA-D8-Pad18)") (class "Default")
      (node (ref "UA") (pin "18") (pinfunction "D8_18") (pintype "input"))
    )
    (net (code "162") (name "unconnected-(UA-Q5-Pad12)") (class "Default")
      (node (ref "UA") (pin "12") (pinfunction "Q5_12") (pintype "output"))
    )
    (net (code "163") (name "unconnected-(UA-Q6-Pad15)") (class "Default")
      (node (ref "UA") (pin "15") (pinfunction "Q6_15") (pintype "output"))
    )
    (net (code "164") (name "unconnected-(UA-Q7-Pad16)") (class "Default")
      (node (ref "UA") (pin "16") (pinfunction "Q7_16") (pintype "output"))
    )
    (net (code "165") (name "unconnected-(UA-Q8-Pad19)") (class "Default")
      (node (ref "UA") (pin "19") (pinfunction "Q8_19") (pintype "output"))
    )
    (net (code "166") (name "unconnected-(UB-D5-Pad13)") (class "Default")
      (node (ref "UB") (pin "13") (pinfunction "D5_13") (pintype "input"))
    )
    (net (code "167") (name "unconnected-(UB-D6-Pad14)") (class "Default")
      (node (ref "UB") (pin "14") (pinfunction "D6_14") (pintype "input"))
    )
    (net (code "168") (name "unconnected-(UB-D7-Pad17)") (class "Default")
      (node (ref "UB") (pin "17") (pinfunction "D7_17") (pintype "input"))
    )
    (net (code "169") (name "unconnected-(UB-D8-Pad18)") (class "Default")
      (node (ref "UB") (pin "18") (pinfunction "D8_18") (pintype "input"))
    )
    (net (code "170") (name "unconnected-(UB-Q5-Pad12)") (class "Default")
      (node (ref "UB") (pin "12") (pinfunction "Q5_12") (pintype "output"))
    )
    (net (code "171") (name "unconnected-(UB-Q6-Pad15)") (class "Default")
      (node (ref "UB") (pin "15") (pinfunction "Q6_15") (pintype "output"))
    )
    (net (code "172") (name "unconnected-(UB-Q7-Pad16)") (class "Default")
      (node (ref "UB") (pin "16") (pinfunction "Q7_16") (pintype "output"))
    )
    (net (code "173") (name "unconnected-(UB-Q8-Pad19)") (class "Default")
      (node (ref "UB") (pin "19") (pinfunction "Q8_19") (pintype "output"))
    )
    (net (code "174") (name "unconnected-(UCALU-2A1-Pad11)") (class "Default")
      (node (ref "UCALU") (pin "11") (pinfunction "2A1_11") (pintype "input"))
    )
    (net (code "175") (name "unconnected-(UCALU-2A2-Pad13)") (class "Default")
      (node (ref "UCALU") (pin "13") (pinfunction "2A2_13") (pintype "input"))
    )
    (net (code "176") (name "unconnected-(UCALU-2A3-Pad15)") (class "Default")
      (node (ref "UCALU") (pin "15") (pinfunction "2A3_15") (pintype "input"))
    )
    (net (code "177") (name "unconnected-(UCALU-2A4-Pad17)") (class "Default")
      (node (ref "UCALU") (pin "17") (pinfunction "2A4_17") (pintype "input"))
    )
    (net (code "178") (name "unconnected-(UCALU-2Y1-Pad9)") (class "Default")
      (node (ref "UCALU") (pin "9") (pinfunction "2Y1_9") (pintype "tri_state"))
    )
    (net (code "179") (name "unconnected-(UCALU-2Y2-Pad7)") (class "Default")
      (node (ref "UCALU") (pin "7") (pinfunction "2Y2_7") (pintype "tri_state"))
    )
    (net (code "180") (name "unconnected-(UCALU-2Y3-Pad5)") (class "Default")
      (node (ref "UCALU") (pin "5") (pinfunction "2Y3_5") (pintype "tri_state"))
    )
    (net (code "181") (name "unconnected-(UCALU-2Y4-Pad3)") (class "Default")
      (node (ref "UCALU") (pin "3") (pinfunction "2Y4_3") (pintype "tri_state"))
    )
    (net (code "182") (name "unconnected-(UCB-2A1-Pad11)") (class "Default")
      (node (ref "UCB") (pin "11") (pinfunction "2A1_11") (pintype "input"))
    )
    (net (code "183") (name "unconnected-(UCB-2A2-Pad13)") (class "Default")
      (node (ref "UCB") (pin "13") (pinfunction "2A2_13") (pintype "input"))
    )
    (net (code "184") (name "unconnected-(UCB-2A3-Pad15)") (class "Default")
      (node (ref "UCB") (pin "15") (pinfunction "2A3_15") (pintype "input"))
    )
    (net (code "185") (name "unconnected-(UCB-2A4-Pad17)") (class "Default")
      (node (ref "UCB") (pin "17") (pinfunction "2A4_17") (pintype "input"))
    )
    (net (code "186") (name "unconnected-(UCB-2Y1-Pad9)") (class "Default")
      (node (ref "UCB") (pin "9") (pinfunction "2Y1_9") (pintype "tri_state"))
    )
    (net (code "187") (name "unconnected-(UCB-2Y2-Pad7)") (class "Default")
      (node (ref "UCB") (pin "7") (pinfunction "2Y2_7") (pintype "tri_state"))
    )
    (net (code "188") (name "unconnected-(UCB-2Y3-Pad5)") (class "Default")
      (node (ref "UCB") (pin "5") (pinfunction "2Y3_5") (pintype "tri_state"))
    )
    (net (code "189") (name "unconnected-(UCB-2Y4-Pad3)") (class "Default")
      (node (ref "UCB") (pin "3") (pinfunction "2Y4_3") (pintype "tri_state"))
    )
  )
)
